# Clock_group.net
KiCad netlist of a schematic drawn in Altium Designer
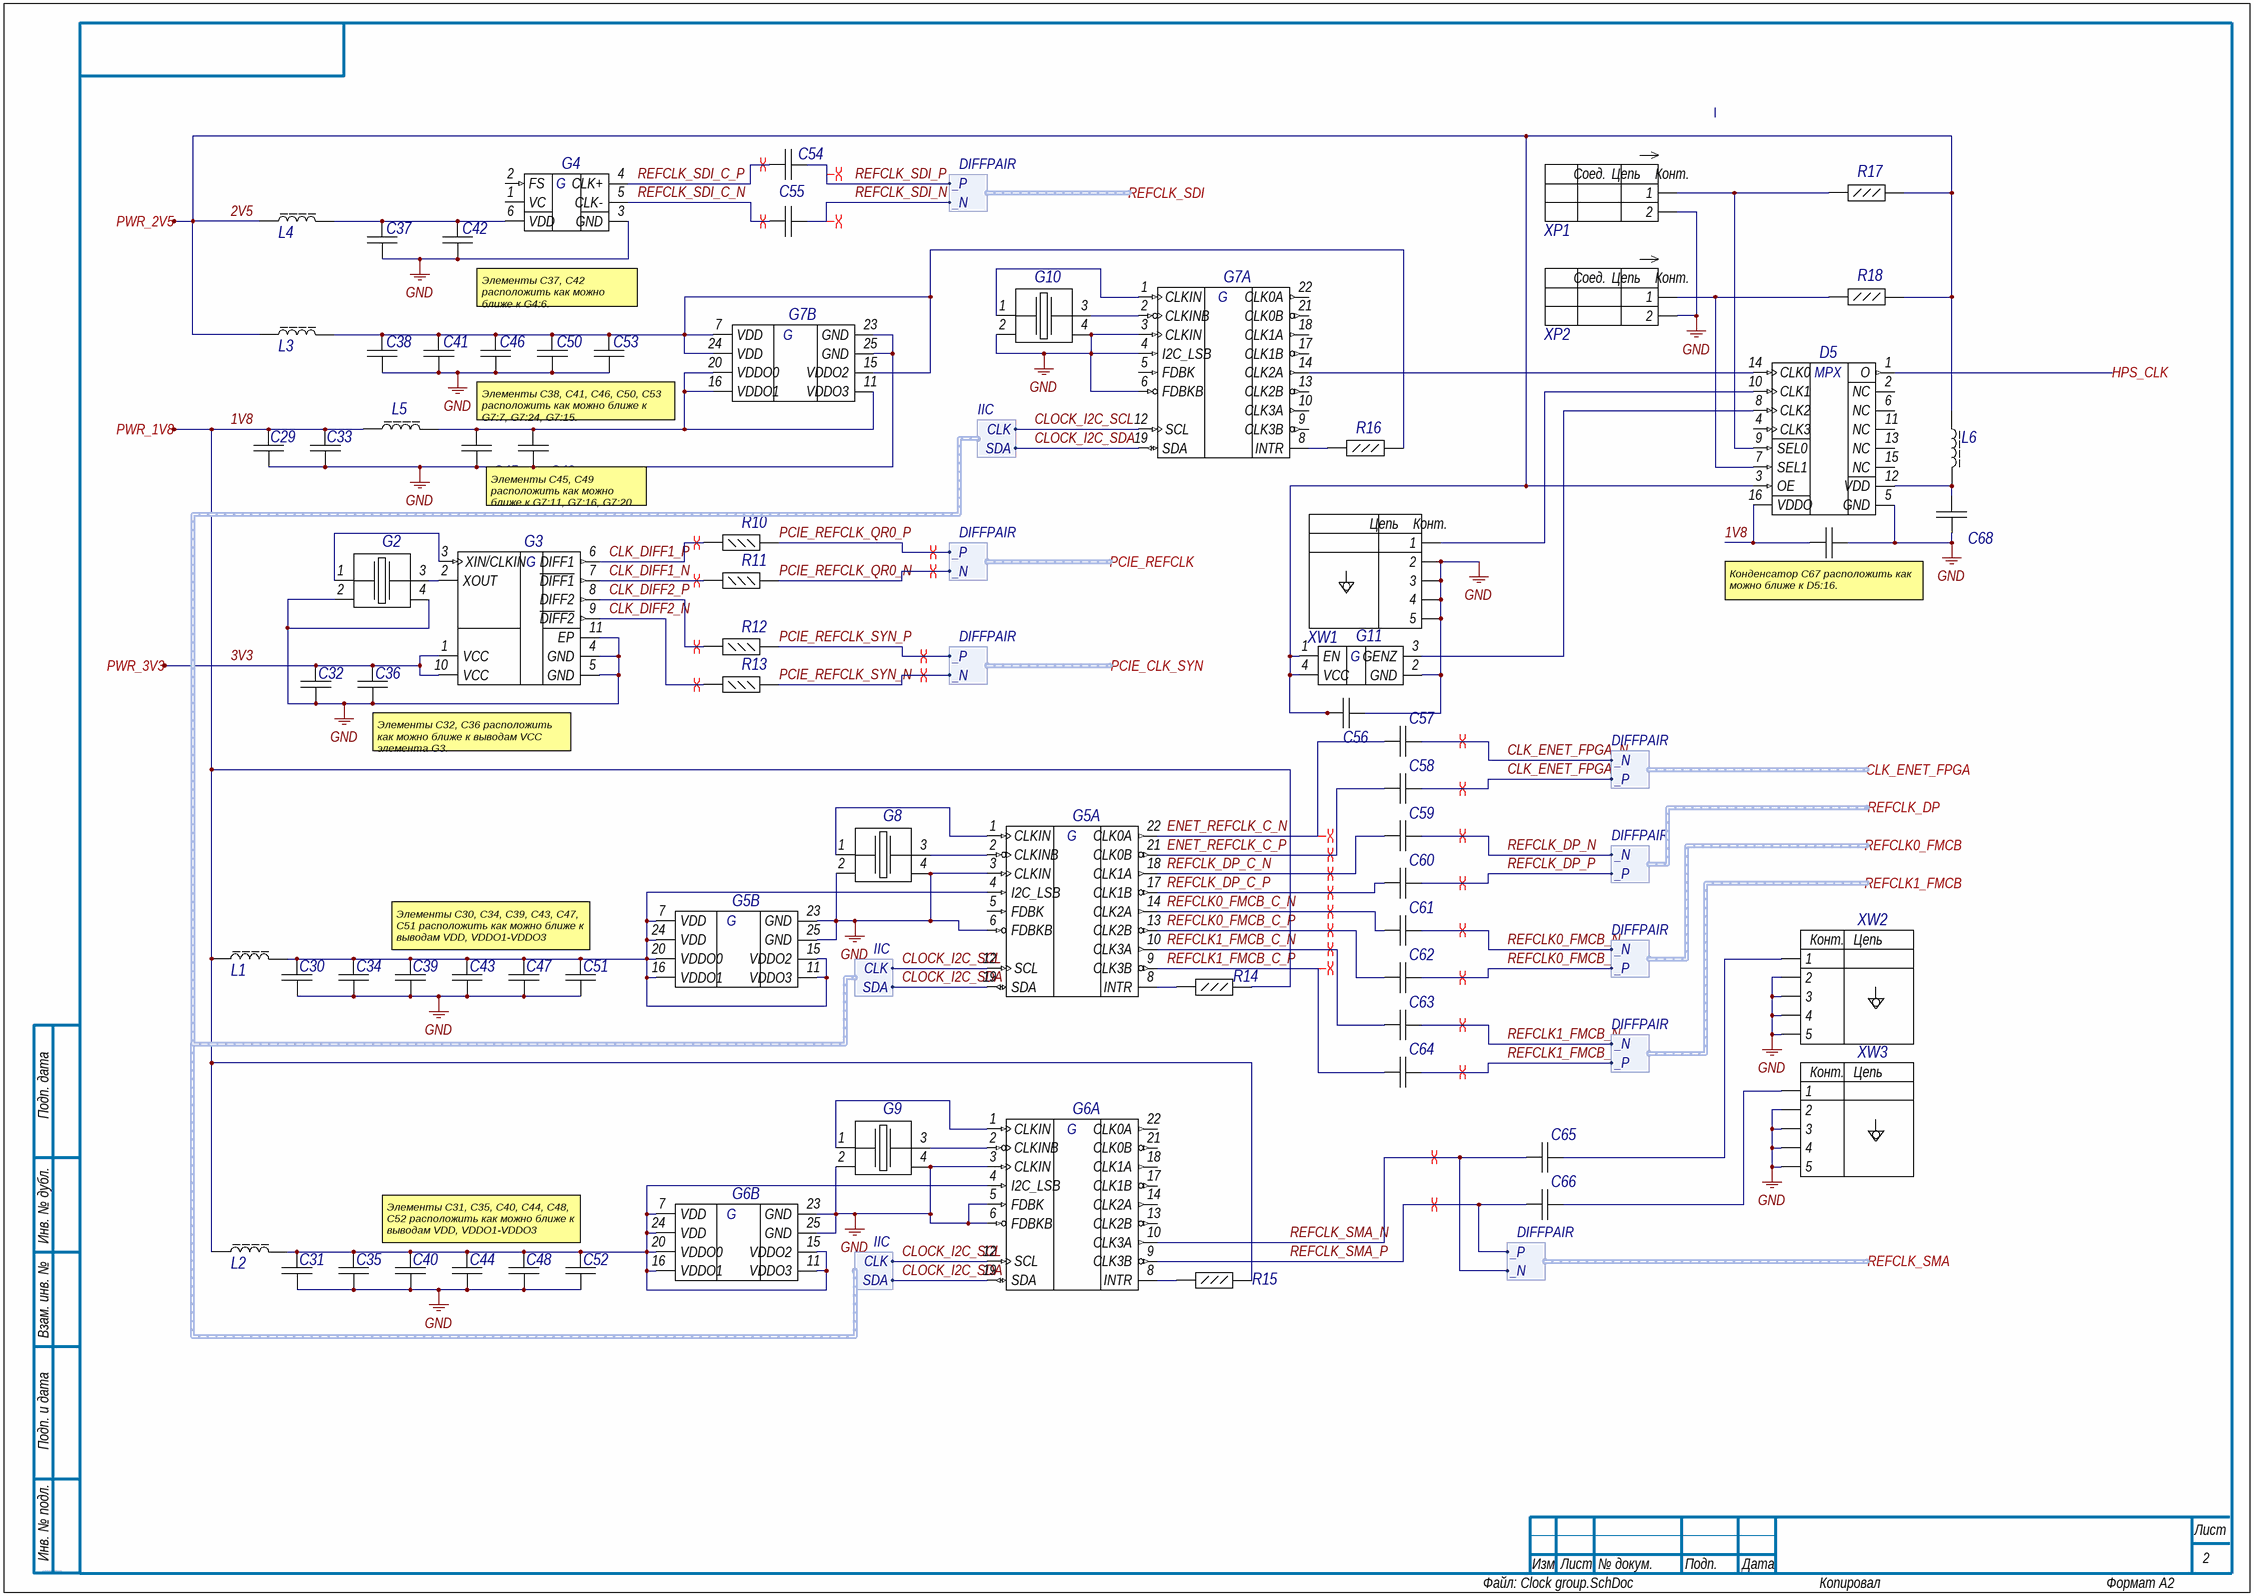
[diagram p0: Clock group.SchDoc]

(export (version "E")
  (design (tool "Eeschema 10.0.6"))
  (components
    (comp (ref "C29")
      (value "C1005X7R1E104M")
      (footprint "CAPC1005X55X10LL05")
      (description "Chip Capacitor, 0.1 uF, +/- 20%, 25 V, -55 to 125 degC, 0402 (1005 Metric), RoHS, Tape and Reel")
      (fields (field (name "TOLERANCE") "20%"))
      (libsource (lib "MiniPC DB") (part "CAP_NP"))
    )
    (comp (ref "C30")
      (value "C1005X7R1E104M")
      (footprint "CAPC1005X55X10LL05")
      (description "Chip Capacitor, 0.1 uF, +/- 20%, 25 V, -55 to 125 degC, 0402 (1005 Metric), RoHS, Tape and Reel")
      (fields (field (name "TOLERANCE") "20%"))
      (libsource (lib "MiniPC DB") (part "CAP_NP"))
    )
    (comp (ref "C31")
      (value "C1005X7R1E104M")
      (footprint "CAPC1005X55X10LL05")
      (description "Chip Capacitor, 0.1 uF, +/- 20%, 25 V, -55 to 125 degC, 0402 (1005 Metric), RoHS, Tape and Reel")
      (fields (field (name "TOLERANCE") "20%"))
      (libsource (lib "MiniPC DB") (part "CAP_NP"))
    )
    (comp (ref "C32")
      (value "C1005X7R1E104M")
      (footprint "CAPC1005X55X10LL05")
      (description "Chip Capacitor, 0.1 uF, +/- 20%, 25 V, -55 to 125 degC, 0402 (1005 Metric), RoHS, Tape and Reel")
      (fields (field (name "TOLERANCE") "20%"))
      (libsource (lib "MiniPC DB") (part "CAP_NP"))
    )
    (comp (ref "C33")
      (value "C1005X7R1E104M")
      (footprint "CAPC1005X55X10LL05")
      (description "Chip Capacitor, 0.1 uF, +/- 20%, 25 V, -55 to 125 degC, 0402 (1005 Metric), RoHS, Tape and Reel")
      (fields (field (name "TOLERANCE") "20%"))
      (libsource (lib "MiniPC DB") (part "CAP_NP"))
    )
    (comp (ref "C34")
      (value "C1005X7R1E104M")
      (footprint "CAPC1005X55X10LL05")
      (description "Chip Capacitor, 0.1 uF, +/- 20%, 25 V, -55 to 125 degC, 0402 (1005 Metric), RoHS, Tape and Reel")
      (fields (field (name "TOLERANCE") "20%"))
      (libsource (lib "MiniPC DB") (part "CAP_NP"))
    )
    (comp (ref "C35")
      (value "C1005X7R1E104M")
      (footprint "CAPC1005X55X10LL05")
      (description "Chip Capacitor, 0.1 uF, +/- 20%, 25 V, -55 to 125 degC, 0402 (1005 Metric), RoHS, Tape and Reel")
      (fields (field (name "TOLERANCE") "20%"))
      (libsource (lib "MiniPC DB") (part "CAP_NP"))
    )
    (comp (ref "C36")
      (value "GRM188R61A225KE34x")
      (footprint "CAPC1608X90X35ML10T15")
      (description "Chip Capacitor, 2.2 uF, +/- 10%, 10 V, -55 to 85 degC, 0603 (1608 Metric), RoHS, Tape and Reel")
      (fields (field (name "TOLERANCE") "10%"))
      (libsource (lib "MiniPC DB") (part "CAP_NP"))
    )
    (comp (ref "C37")
      (value "C2012X5R1C106K085AC")
      (footprint "CAPC2013X100X20NL20")
      (description "Chip Capacitor, 10 uF, +/- 10%, 16 V, -55 to 85 degC, 0805 (2012 Metric), RoHS, Tape and Reel")
      (fields (field (name "TOLERANCE") "10%"))
      (libsource (lib "MiniPC DB") (part "CAP_NP"))
    )
    (comp (ref "C38")
      (value "C1005X7R1E104M")
      (footprint "CAPC1005X55X10LL05")
      (description "Chip Capacitor, 0.1 uF, +/- 20%, 25 V, -55 to 125 degC, 0402 (1005 Metric), RoHS, Tape and Reel")
      (fields (field (name "TOLERANCE") "20%"))
      (libsource (lib "MiniPC DB") (part "CAP_NP"))
    )
    (comp (ref "C39")
      (value "C1005X7R1E104M")
      (footprint "CAPC1005X55X10LL05")
      (description "Chip Capacitor, 0.1 uF, +/- 20%, 25 V, -55 to 125 degC, 0402 (1005 Metric), RoHS, Tape and Reel")
      (fields (field (name "TOLERANCE") "20%"))
      (libsource (lib "MiniPC DB") (part "CAP_NP"))
    )
    (comp (ref "C40")
      (value "C1005X7R1E104M")
      (footprint "CAPC1005X55X10LL05")
      (description "Chip Capacitor, 0.1 uF, +/- 20%, 25 V, -55 to 125 degC, 0402 (1005 Metric), RoHS, Tape and Reel")
      (fields (field (name "TOLERANCE") "20%"))
      (libsource (lib "MiniPC DB") (part "CAP_NP"))
    )
    (comp (ref "C41")
      (value "C1005X7R1E104M")
      (footprint "CAPC1005X55X10LL05")
      (description "Chip Capacitor, 0.1 uF, +/- 20%, 25 V, -55 to 125 degC, 0402 (1005 Metric), RoHS, Tape and Reel")
      (fields (field (name "TOLERANCE") "20%"))
      (libsource (lib "MiniPC DB") (part "CAP_NP"))
    )
    (comp (ref "C42")
      (value "C1005X7R1E104M")
      (footprint "CAPC1005X55X10LL05")
      (description "Chip Capacitor, 0.1 uF, +/- 20%, 25 V, -55 to 125 degC, 0402 (1005 Metric), RoHS, Tape and Reel")
      (fields (field (name "TOLERANCE") "20%"))
      (libsource (lib "MiniPC DB") (part "CAP_NP"))
    )
    (comp (ref "C43")
      (value "C1005X7R1E104M")
      (footprint "CAPC1005X55X10LL05")
      (description "Chip Capacitor, 0.1 uF, +/- 20%, 25 V, -55 to 125 degC, 0402 (1005 Metric), RoHS, Tape and Reel")
      (fields (field (name "TOLERANCE") "20%"))
      (libsource (lib "MiniPC DB") (part "CAP_NP"))
    )
    (comp (ref "C44")
      (value "C1005X7R1E104M")
      (footprint "CAPC1005X55X10LL05")
      (description "Chip Capacitor, 0.1 uF, +/- 20%, 25 V, -55 to 125 degC, 0402 (1005 Metric), RoHS, Tape and Reel")
      (fields (field (name "TOLERANCE") "20%"))
      (libsource (lib "MiniPC DB") (part "CAP_NP"))
    )
    (comp (ref "C45")
      (value "C1005X7R1E104M")
      (footprint "CAPC1005X55X10LL05")
      (description "Chip Capacitor, 0.1 uF, +/- 20%, 25 V, -55 to 125 degC, 0402 (1005 Metric), RoHS, Tape and Reel")
      (fields (field (name "TOLERANCE") "20%"))
      (libsource (lib "MiniPC DB") (part "CAP_NP"))
    )
    (comp (ref "C46")
      (value "C1005X7R1E104M")
      (footprint "CAPC1005X55X10LL05")
      (description "Chip Capacitor, 0.1 uF, +/- 20%, 25 V, -55 to 125 degC, 0402 (1005 Metric), RoHS, Tape and Reel")
      (fields (field (name "TOLERANCE") "20%"))
      (libsource (lib "MiniPC DB") (part "CAP_NP"))
    )
    (comp (ref "C47")
      (value "C1005X7R1E104M")
      (footprint "CAPC1005X55X10LL05")
      (description "Chip Capacitor, 0.1 uF, +/- 20%, 25 V, -55 to 125 degC, 0402 (1005 Metric), RoHS, Tape and Reel")
      (fields (field (name "TOLERANCE") "20%"))
      (libsource (lib "MiniPC DB") (part "CAP_NP"))
    )
    (comp (ref "C48")
      (value "C1005X7R1E104M")
      (footprint "CAPC1005X55X10LL05")
      (description "Chip Capacitor, 0.1 uF, +/- 20%, 25 V, -55 to 125 degC, 0402 (1005 Metric), RoHS, Tape and Reel")
      (fields (field (name "TOLERANCE") "20%"))
      (libsource (lib "MiniPC DB") (part "CAP_NP"))
    )
    (comp (ref "C49")
      (value "C1005X7R1E104M")
      (footprint "CAPC1005X55X10LL05")
      (description "Chip Capacitor, 0.1 uF, +/- 20%, 25 V, -55 to 125 degC, 0402 (1005 Metric), RoHS, Tape and Reel")
      (fields (field (name "TOLERANCE") "20%"))
      (libsource (lib "MiniPC DB") (part "CAP_NP"))
    )
    (comp (ref "C50")
      (value "C1005X7R1E104M")
      (footprint "CAPC1005X55X10LL05")
      (description "Chip Capacitor, 0.1 uF, +/- 20%, 25 V, -55 to 125 degC, 0402 (1005 Metric), RoHS, Tape and Reel")
      (fields (field (name "TOLERANCE") "20%"))
      (libsource (lib "MiniPC DB") (part "CAP_NP"))
    )
    (comp (ref "C51")
      (value "C1005X7R1E104M")
      (footprint "CAPC1005X55X10LL05")
      (description "Chip Capacitor, 0.1 uF, +/- 20%, 25 V, -55 to 125 degC, 0402 (1005 Metric), RoHS, Tape and Reel")
      (fields (field (name "TOLERANCE") "20%"))
      (libsource (lib "MiniPC DB") (part "CAP_NP"))
    )
    (comp (ref "C52")
      (value "C1005X7R1E104M")
      (footprint "CAPC1005X55X10LL05")
      (description "Chip Capacitor, 0.1 uF, +/- 20%, 25 V, -55 to 125 degC, 0402 (1005 Metric), RoHS, Tape and Reel")
      (fields (field (name "TOLERANCE") "20%"))
      (libsource (lib "MiniPC DB") (part "CAP_NP"))
    )
    (comp (ref "C53")
      (value "C1005X7R1E104M")
      (footprint "CAPC1005X55X10LL05")
      (description "Chip Capacitor, 0.1 uF, +/- 20%, 25 V, -55 to 125 degC, 0402 (1005 Metric), RoHS, Tape and Reel")
      (fields (field (name "TOLERANCE") "20%"))
      (libsource (lib "MiniPC DB") (part "CAP_NP"))
    )
    (comp (ref "C54")
      (value "C1005X7R1E104M")
      (footprint "CAPC1005X55X10LL05")
      (description "Chip Capacitor, 0.1 uF, +/- 20%, 25 V, -55 to 125 degC, 0402 (1005 Metric), RoHS, Tape and Reel")
      (fields (field (name "TOLERANCE") "20%"))
      (libsource (lib "MiniPC DB") (part "CAP_NP"))
    )
    (comp (ref "C55")
      (value "C1005X7R1E104M")
      (footprint "CAPC1005X55X10LL05")
      (description "Chip Capacitor, 0.1 uF, +/- 20%, 25 V, -55 to 125 degC, 0402 (1005 Metric), RoHS, Tape and Reel")
      (fields (field (name "TOLERANCE") "20%"))
      (libsource (lib "MiniPC DB") (part "CAP_NP"))
    )
    (comp (ref "C56")
      (value "GRM155R71H103KA88D")
      (footprint "CAPC1005X55X25ML05T10")
      (description "Chip Capacitor, 10 nF, +/- 10%, 50 V, -55 to 125 degC, 0402 (1005 Metric), RoHS, Tape and Reel")
      (fields (field (name "TOLERANCE") "10%") (field (name "MANUFACTURER") "Basic Passives"))
      (libsource (lib "MiniPC DB") (part "CAP_NP"))
    )
    (comp (ref "C57")
      (value "C1005X7R1E104M")
      (footprint "CAPC1005X55X10LL05")
      (description "Chip Capacitor, 0.1 uF, +/- 20%, 25 V, -55 to 125 degC, 0402 (1005 Metric), RoHS, Tape and Reel")
      (fields (field (name "TOLERANCE") "20%"))
      (libsource (lib "MiniPC DB") (part "CAP_NP"))
    )
    (comp (ref "C58")
      (value "C1005X7R1E104M")
      (footprint "CAPC1005X55X10LL05")
      (description "Chip Capacitor, 0.1 uF, +/- 20%, 25 V, -55 to 125 degC, 0402 (1005 Metric), RoHS, Tape and Reel")
      (fields (field (name "TOLERANCE") "20%"))
      (libsource (lib "MiniPC DB") (part "CAP_NP"))
    )
    (comp (ref "C59")
      (value "C1005X7R1E104M")
      (footprint "CAPC1005X55X10LL05")
      (description "Chip Capacitor, 0.1 uF, +/- 20%, 25 V, -55 to 125 degC, 0402 (1005 Metric), RoHS, Tape and Reel")
      (fields (field (name "TOLERANCE") "20%"))
      (libsource (lib "MiniPC DB") (part "CAP_NP"))
    )
    (comp (ref "C60")
      (value "C1005X7R1E104M")
      (footprint "CAPC1005X55X10LL05")
      (description "Chip Capacitor, 0.1 uF, +/- 20%, 25 V, -55 to 125 degC, 0402 (1005 Metric), RoHS, Tape and Reel")
      (fields (field (name "TOLERANCE") "20%"))
      (libsource (lib "MiniPC DB") (part "CAP_NP"))
    )
    (comp (ref "C61")
      (value "C1005X7R1E104M")
      (footprint "CAPC1005X55X10LL05")
      (description "Chip Capacitor, 0.1 uF, +/- 20%, 25 V, -55 to 125 degC, 0402 (1005 Metric), RoHS, Tape and Reel")
      (fields (field (name "TOLERANCE") "20%"))
      (libsource (lib "MiniPC DB") (part "CAP_NP"))
    )
    (comp (ref "C62")
      (value "C1005X7R1E104M")
      (footprint "CAPC1005X55X10LL05")
      (description "Chip Capacitor, 0.1 uF, +/- 20%, 25 V, -55 to 125 degC, 0402 (1005 Metric), RoHS, Tape and Reel")
      (fields (field (name "TOLERANCE") "20%"))
      (libsource (lib "MiniPC DB") (part "CAP_NP"))
    )
    (comp (ref "C63")
      (value "C1005X7R1E104M")
      (footprint "CAPC1005X55X10LL05")
      (description "Chip Capacitor, 0.1 uF, +/- 20%, 25 V, -55 to 125 degC, 0402 (1005 Metric), RoHS, Tape and Reel")
      (fields (field (name "TOLERANCE") "20%"))
      (libsource (lib "MiniPC DB") (part "CAP_NP"))
    )
    (comp (ref "C64")
      (value "C1005X7R1E104M")
      (footprint "CAPC1005X55X10LL05")
      (description "Chip Capacitor, 0.1 uF, +/- 20%, 25 V, -55 to 125 degC, 0402 (1005 Metric), RoHS, Tape and Reel")
      (fields (field (name "TOLERANCE") "20%"))
      (libsource (lib "MiniPC DB") (part "CAP_NP"))
    )
    (comp (ref "C65")
      (value "C1005X7R1E104M")
      (footprint "CAPC1005X55X10LL05")
      (description "Chip Capacitor, 0.1 uF, +/- 20%, 25 V, -55 to 125 degC, 0402 (1005 Metric), RoHS, Tape and Reel")
      (fields (field (name "TOLERANCE") "20%"))
      (libsource (lib "MiniPC DB") (part "CAP_NP"))
    )
    (comp (ref "C66")
      (value "C1005X7R1E104M")
      (footprint "CAPC1005X55X10LL05")
      (description "Chip Capacitor, 0.1 uF, +/- 20%, 25 V, -55 to 125 degC, 0402 (1005 Metric), RoHS, Tape and Reel")
      (fields (field (name "TOLERANCE") "20%"))
      (libsource (lib "MiniPC DB") (part "CAP_NP"))
    )
    (comp (ref "C67")
      (value "C1005X7R1E104M")
      (footprint "CAPC1005X55X10LL05")
      (description "Chip Capacitor, 0.1 uF, +/- 20%, 25 V, -55 to 125 degC, 0402 (1005 Metric), RoHS, Tape and Reel")
      (fields (field (name "TOLERANCE") "20%"))
      (libsource (lib "MiniPC DB") (part "CAP_NP"))
    )
    (comp (ref "C68")
      (value "C1005X7R1E104M")
      (footprint "CAPC1005X55X10LL05")
      (description "Chip Capacitor, 0.1 uF, +/- 20%, 25 V, -55 to 125 degC, 0402 (1005 Metric), RoHS, Tape and Reel")
      (fields (field (name "TOLERANCE") "20%"))
      (libsource (lib "MiniPC DB") (part "CAP_NP"))
    )
    (comp (ref "D5")
      (value "ICS83054AGILF")
      (footprint "IDT-TSSOP-16_M")
      (description "Single-Ended Multiplexer, 2.375 to 3.465 V, -40 to 85 degC, 16-Pin TSSOP, RoHS, Tube")
      (fields (field (name "MANUFACTURER") "IDT"))
      (libsource (lib "MiniPC DB") (part "ICS83054I"))
    )
    (comp (ref "G2")
      (value "FA-128 25.0000MB-C")
      (footprint "EPSON-FA-128_V")
      (description "Range Crystal Unit, 25 MHz, -40 to 85 degC, 4-Pin SMD, RoHS, Tape and Reel")
      (libsource (lib "MiniPC DB") (part "OSC_4K"))
    )
    (comp (ref "G3")
      (value "Si52112-A1-GM2")
      (footprint "SLAB-TDFN-10_L")
      (fields (field (name "MANUFACTURER") "Silicon Labs"))
      (libsource (lib "MiniPC DB") (part "Si52112"))
    )
    (comp (ref "G4")
      (value "516FHA000132AAG")
      (footprint "SLAB-DFN-6-5000X7000DE_A_V")
      (fields (field (name "MANUFACTURER") "Silicon Labs"))
      (libsource (lib "MiniPC DB") (part "516FHA"))
    )
    (comp (ref "G5")
      (value "Si5338B-B03799-GM")
      (footprint "SLAB-QFN-24-2550x2550TP_V")
      (fields (field (name "MANUFACTURER") "Silicon Labs"))
      (libsource (lib "MiniPC DB") (part "Si5338"))
    )
    (comp (ref "G6")
      (value "Si5338B-B03799-GM")
      (footprint "SLAB-QFN-24-2550x2550TP_V")
      (fields (field (name "MANUFACTURER") "Silicon Labs"))
      (libsource (lib "MiniPC DB") (part "Si5338"))
    )
    (comp (ref "G7")
      (value "Si5338C-B03798-GM")
      (footprint "SLAB-QFN-24-2550x2550TP_V")
      (fields (field (name "MANUFACTURER") "Silicon Labs"))
      (libsource (lib "MiniPC DB") (part "Si5338"))
    )
    (comp (ref "G8")
      (value "FA-128 25.0000MB-C")
      (footprint "EPSON-FA-128_V")
      (description "Range Crystal Unit, 25 MHz, -40 to 85 degC, 4-Pin SMD, RoHS, Tape and Reel")
      (libsource (lib "MiniPC DB") (part "OSC_4K"))
    )
    (comp (ref "G9")
      (value "FA-128 25.0000MB-C")
      (footprint "EPSON-FA-128_V")
      (description "Range Crystal Unit, 25 MHz, -40 to 85 degC, 4-Pin SMD, RoHS, Tape and Reel")
      (libsource (lib "MiniPC DB") (part "OSC_4K"))
    )
    (comp (ref "G10")
      (value "FA-128 25.0000MB-C")
      (footprint "EPSON-FA-128_V")
      (description "Range Crystal Unit, 25 MHz, -40 to 85 degC, 4-Pin SMD, RoHS, Tape and Reel")
      (libsource (lib "MiniPC DB") (part "OSC_4K"))
    )
    (comp (ref "G11")
      (value "ASE2-33.000MHZ-ET")
      (footprint "ABRA-ASE2_V")
      (fields (field (name "MANUFACTURER") "Abracon"))
      (libsource (lib "MiniPC DB") (part "ASE2"))
    )
    (comp (ref "L1")
      (value "BLM15AG221SN1J")
      (footprint "MURA-BLM15-CHIP-2_V")
      (fields (field (name "MANUFACTURER") "Murata"))
      (libsource (lib "MiniPC DB") (part "Choke"))
    )
    (comp (ref "L2")
      (value "BLM15AG221SN1x")
      (footprint "MURA-BLM15AG221SN1x_V")
      (description "Chip Bead, 220 Ohm, +/- 25 %, 100 MHz, 300 mA, -55 to 125 degC, 0402 (1005 Metric), RoHS")
      (fields (field (name "TOLERANCE") "25%"))
      (libsource (lib "MiniPC DB") (part "Choke"))
    )
    (comp (ref "L3")
      (value "742792780")
      (footprint "SMD-0402")
      (description "SMD EMI Suppression Ferrite Bead WE-CBF, Z = 220 Ohm")
      (libsource (lib "") (part "Choke_1"))
    )
    (comp (ref "L4")
      (value "BLM15AG221SN1x")
      (footprint "MURA-BLM15AG221SN1x_V")
      (description "Chip Bead, 220 Ohm, +/- 25 %, 100 MHz, 300 mA, -55 to 125 degC, 0402 (1005 Metric), RoHS")
      (fields (field (name "TOLERANCE") "25%"))
      (libsource (lib "") (part "Choke_1"))
    )
    (comp (ref "L5")
      (value "742792780")
      (footprint "SMD-0402")
      (description "SMD EMI Suppression Ferrite Bead WE-CBF, Z = 220 Ohm")
      (libsource (lib "MiniPC DB") (part "Choke"))
    )
    (comp (ref "L6")
      (value "742792780")
      (footprint "SMD-0402")
      (description "SMD EMI Suppression Ferrite Bead WE-CBF, Z = 220 Ohm")
      (libsource (lib "") (part "Choke_2"))
    )
    (comp (ref "R10")
      (value "ERJ-2GE0R00X")
      (footprint "RESC1005X40X25LL05T05")
      (description "Chip Resistor, 0 mOhm, +/- 5%, 100 mW, -55 to 155 degC, 0402 (1005 Metric), RoHS, Tape and Reel")
      (fields (field (name "TOLERANCE") "5%") (field (name "MANUFACTURER") "Basic Passives"))
      (libsource (lib "MiniPC DB") (part "RES-0.05"))
    )
    (comp (ref "R11")
      (value "ERJ-2GE0R00X")
      (footprint "RESC1005X40X25LL05T05")
      (description "Chip Resistor, 0 mOhm, +/- 5%, 100 mW, -55 to 155 degC, 0402 (1005 Metric), RoHS, Tape and Reel")
      (fields (field (name "TOLERANCE") "5%") (field (name "MANUFACTURER") "Basic Passives"))
      (libsource (lib "MiniPC DB") (part "RES-0.05"))
    )
    (comp (ref "R12")
      (value "ERJ-2GE0R00X")
      (footprint "RESC1005X40X25LL05T05")
      (description "Chip Resistor, 0 mOhm, +/- 5%, 100 mW, -55 to 155 degC, 0402 (1005 Metric), RoHS, Tape and Reel")
      (fields (field (name "TOLERANCE") "5%") (field (name "MANUFACTURER") "Basic Passives"))
      (libsource (lib "MiniPC DB") (part "RES-0.05"))
    )
    (comp (ref "R13")
      (value "ERJ-2GE0R00X")
      (footprint "RESC1005X40X25LL05T05")
      (description "Chip Resistor, 0 mOhm, +/- 5%, 100 mW, -55 to 155 degC, 0402 (1005 Metric), RoHS, Tape and Reel")
      (fields (field (name "TOLERANCE") "5%") (field (name "MANUFACTURER") "Basic Passives"))
      (libsource (lib "MiniPC DB") (part "RES-0.05"))
    )
    (comp (ref "R14")
      (value "ERJ-2RKF4701X")
      (footprint "RESC1005X40X25LL05T05")
      (description "Chip Resistor, 4.7 KOhm, +/- 1%, 0.1 W, -55 to 155 degC, 0402 (1005 Metric), RoHS, Tape and Reel")
      (fields (field (name "TOLERANCE") "1%"))
      (libsource (lib "") (part "RES-0.05_1"))
    )
    (comp (ref "R15")
      (value "ERJ-2RKF4701X")
      (footprint "RESC1005X40X25LL05T05")
      (description "Chip Resistor, 4.7 KOhm, +/- 1%, 0.1 W, -55 to 155 degC, 0402 (1005 Metric), RoHS, Tape and Reel")
      (fields (field (name "TOLERANCE") "1%"))
      (libsource (lib "") (part "RES-0.05_1"))
    )
    (comp (ref "R16")
      (value "ERJ-2RKF1001X")
      (footprint "RESC1005X40X25LL05T05")
      (description "Chip Resistor, 1 KOhm, +/- 1%, 100 mW, -55 to 155 degC, 0402 (1005 Metric), RoHS, Tape and Reel")
      (fields (field (name "TOLERANCE") "1%") (field (name "MANUFACTURER") "Basic Passives"))
      (libsource (lib "") (part "RES-0.05_1"))
    )
    (comp (ref "R17")
      (value "ERJ-2RKF1001X")
      (footprint "RESC1005X40X25LL05T05")
      (description "Chip Resistor, 1 KOhm, +/- 1%, 100 mW, -55 to 155 degC, 0402 (1005 Metric), RoHS, Tape and Reel")
      (fields (field (name "TOLERANCE") "1%") (field (name "MANUFACTURER") "Basic Passives"))
      (libsource (lib "") (part "RES-0.05_1"))
    )
    (comp (ref "R18")
      (value "ERJ-2RKF1001X")
      (footprint "RESC1005X40X25LL05T05")
      (description "Chip Resistor, 1 KOhm, +/- 1%, 100 mW, -55 to 155 degC, 0402 (1005 Metric), RoHS, Tape and Reel")
      (fields (field (name "TOLERANCE") "1%") (field (name "MANUFACTURER") "Basic Passives"))
      (libsource (lib "") (part "RES-0.05_1"))
    )
    (comp (ref "XP1")
      (value "613 002 111 21")
      (footprint "WE-61300211121_V")
      (fields (field (name "MANUFACTURER") "Wuerth Elektronik"))
      (libsource (lib "MiniPC DB") (part "VILKA_2K"))
    )
    (comp (ref "XP2")
      (value "613 002 111 21")
      (footprint "WE-61300211121_V")
      (fields (field (name "MANUFACTURER") "Wuerth Elektronik"))
      (libsource (lib "MiniPC DB") (part "VILKA_2K"))
    )
    (comp (ref "XW1")
      (value "LTI-SASF54GT")
      (footprint "LHT-LTI-SASF54GT_V")
      (description "SMA Connector, Pitch 2.54 mm, 1 Position, Height 9.5 mm, Tail Length 4 mm, RoHS")
      (fields (field (name "MANUFACTURER") "Lighthorse Technologies Inc."))
      (libsource (lib "") (part "ROZETKA_SMA5_PCB_1"))
    )
    (comp (ref "XW2")
      (value "LTI-SASF54GT")
      (footprint "LHT-LTI-SASF54GT_V")
      (description "SMA Connector, Pitch 2.54 mm, 1 Position, Height 9.5 mm, Tail Length 4 mm, RoHS")
      (fields (field (name "MANUFACTURER") "Lighthorse Technologies Inc."))
      (libsource (lib "MiniPC DB") (part "ROZETKA_SMA5_PCB"))
    )
    (comp (ref "XW3")
      (value "LTI-SASF54GT")
      (footprint "LHT-LTI-SASF54GT_V")
      (description "SMA Connector, Pitch 2.54 mm, 1 Position, Height 9.5 mm, Tail Length 4 mm, RoHS")
      (fields (field (name "MANUFACTURER") "Lighthorse Technologies Inc."))
      (libsource (lib "MiniPC DB") (part "ROZETKA_SMA5_PCB"))
    )
  )
  (nets
    (net (code "3") (name "/1V8") (class "Default")
      (node (ref "C29") (pin "2") (pinfunction "2_2") (pintype "passive"))
      (node (ref "C33") (pin "2") (pinfunction "2_2") (pintype "passive"))
      (node (ref "C67") (pin "2") (pinfunction "2_2") (pintype "passive"))
      (node (ref "D5") (pin "16") (pinfunction "VDDO_16") (pintype "power_in"))
      (node (ref "L1") (pin "2") (pinfunction "2_2") (pintype "passive"))
      (node (ref "L2") (pin "2") (pinfunction "2_2") (pintype "passive"))
      (node (ref "L5") (pin "2") (pinfunction "2_2") (pintype "passive"))
      (node (ref "R14") (pin "1") (pinfunction "1_1") (pintype "passive"))
      (node (ref "R15") (pin "1") (pinfunction "1_1") (pintype "passive"))
    )
    (net (code "4") (name "/2V5") (class "Default")
      (node (ref "C56") (pin "2") (pinfunction "2_2") (pintype "passive"))
      (node (ref "D5") (pin "3") (pinfunction "OE_3") (pintype "input"))
      (node (ref "G11") (pin "1") (pinfunction "EN_1") (pintype "passive"))
      (node (ref "G11") (pin "4") (pinfunction "VCC_4") (pintype "passive"))
      (node (ref "L3") (pin "2") (pinfunction "2_2") (pintype "passive"))
      (node (ref "L4") (pin "2") (pinfunction "2_2") (pintype "passive"))
      (node (ref "L6") (pin "2") (pinfunction "2_2") (pintype "passive"))
      (node (ref "R17") (pin "1") (pinfunction "1_1") (pintype "passive"))
      (node (ref "R18") (pin "1") (pinfunction "1_1") (pintype "passive"))
    )
    (net (code "5") (name "/3V3") (class "Default")
      (node (ref "C32") (pin "2") (pinfunction "2_2") (pintype "passive"))
      (node (ref "C36") (pin "2") (pinfunction "2_2") (pintype "passive"))
      (node (ref "G3") (pin "1") (pinfunction "VCC_1") (pintype "passive"))
      (node (ref "G3") (pin "10") (pinfunction "VCC_10") (pintype "passive"))
    )
    (net (code "6") (name "/CLK_DIFF1_N") (class "Default")
      (node (ref "G3") (pin "7") (pinfunction "~{DIFF1}_7") (pintype "output"))
      (node (ref "R11") (pin "1") (pinfunction "1_1") (pintype "passive"))
    )
    (net (code "7") (name "/CLK_DIFF1_P") (class "Default")
      (node (ref "G3") (pin "6") (pinfunction "DIFF1_6") (pintype "output"))
      (node (ref "R10") (pin "1") (pinfunction "1_1") (pintype "passive"))
    )
    (net (code "8") (name "/CLK_DIFF2_N") (class "Default")
      (node (ref "G3") (pin "9") (pinfunction "~{DIFF2}_9") (pintype "output"))
      (node (ref "R13") (pin "1") (pinfunction "1_1") (pintype "passive"))
    )
    (net (code "9") (name "/CLK_DIFF2_P") (class "Default")
      (node (ref "G3") (pin "8") (pinfunction "DIFF2_8") (pintype "output"))
      (node (ref "R12") (pin "1") (pinfunction "1_1") (pintype "passive"))
    )
    (net (code "10") (name "/CLK_ENET_FPGA_N") (class "Default")
      (node (ref "C57") (pin "2") (pinfunction "2_2") (pintype "passive"))
    )
    (net (code "11") (name "/CLK_ENET_FPGA_P") (class "Default")
      (node (ref "C58") (pin "2") (pinfunction "2_2") (pintype "passive"))
    )
    (net (code "12") (name "/CLOCK_I2C_SCL") (class "Default")
      (node (ref "G5") (pin "12") (pinfunction "SCL_12") (pintype "input"))
      (node (ref "G6") (pin "12") (pinfunction "SCL_12") (pintype "input"))
      (node (ref "G7") (pin "12") (pinfunction "SCL_12") (pintype "input"))
    )
    (net (code "13") (name "/CLOCK_I2C_SDA") (class "Default")
      (node (ref "G5") (pin "19") (pinfunction "SDA_19") (pintype "bidirectional"))
      (node (ref "G6") (pin "19") (pinfunction "SDA_19") (pintype "bidirectional"))
      (node (ref "G7") (pin "19") (pinfunction "SDA_19") (pintype "bidirectional"))
    )
    (net (code "14") (name "/ENET_REFCLK_C_N") (class "Default")
      (node (ref "C57") (pin "1") (pinfunction "1_1") (pintype "passive"))
      (node (ref "G5") (pin "22") (pinfunction "CLK0A_22") (pintype "output"))
    )
    (net (code "15") (name "/ENET_REFCLK_C_P") (class "Default")
      (node (ref "C58") (pin "1") (pinfunction "1_1") (pintype "passive"))
      (node (ref "G5") (pin "21") (pinfunction "CLK0B_21") (pintype "output"))
    )
    (net (code "16") (name "/HPS_CLK") (class "Default")
      (node (ref "D5") (pin "1") (pinfunction "O_1") (pintype "output"))
    )
    (net (code "17") (name "/PCIE_REFCLK_QR0_N") (class "Default")
      (node (ref "R11") (pin "2") (pinfunction "2_2") (pintype "passive"))
    )
    (net (code "18") (name "/PCIE_REFCLK_QR0_P") (class "Default")
      (node (ref "R10") (pin "2") (pinfunction "2_2") (pintype "passive"))
    )
    (net (code "19") (name "/PCIE_REFCLK_SYN_N") (class "Default")
      (node (ref "R13") (pin "2") (pinfunction "2_2") (pintype "passive"))
    )
    (net (code "20") (name "/PCIE_REFCLK_SYN_P") (class "Default")
      (node (ref "R12") (pin "2") (pinfunction "2_2") (pintype "passive"))
    )
    (net (code "21") (name "/REFCLK0_FMCB_C_N") (class "Default")
      (node (ref "C61") (pin "1") (pinfunction "1_1") (pintype "passive"))
      (node (ref "G5") (pin "14") (pinfunction "CLK2A_14") (pintype "output"))
    )
    (net (code "22") (name "/REFCLK0_FMCB_C_P") (class "Default")
      (node (ref "C62") (pin "1") (pinfunction "1_1") (pintype "passive"))
      (node (ref "G5") (pin "13") (pinfunction "CLK2B_13") (pintype "output"))
    )
    (net (code "23") (name "/REFCLK0_FMCB_N") (class "Default")
      (node (ref "C61") (pin "2") (pinfunction "2_2") (pintype "passive"))
    )
    (net (code "24") (name "/REFCLK0_FMCB_P") (class "Default")
      (node (ref "C62") (pin "2") (pinfunction "2_2") (pintype "passive"))
    )
    (net (code "25") (name "/REFCLK1_FMCB_C_N") (class "Default")
      (node (ref "C63") (pin "1") (pinfunction "1_1") (pintype "passive"))
      (node (ref "G5") (pin "10") (pinfunction "CLK3A_10") (pintype "output"))
    )
    (net (code "26") (name "/REFCLK1_FMCB_C_P") (class "Default")
      (node (ref "C64") (pin "1") (pinfunction "1_1") (pintype "passive"))
      (node (ref "G5") (pin "9") (pinfunction "CLK3B_9") (pintype "output"))
    )
    (net (code "27") (name "/REFCLK1_FMCB_N") (class "Default")
      (node (ref "C63") (pin "2") (pinfunction "2_2") (pintype "passive"))
    )
    (net (code "28") (name "/REFCLK1_FMCB_P") (class "Default")
      (node (ref "C64") (pin "2") (pinfunction "2_2") (pintype "passive"))
    )
    (net (code "29") (name "/REFCLK_DP_C_N") (class "Default")
      (node (ref "C59") (pin "1") (pinfunction "1_1") (pintype "passive"))
      (node (ref "G5") (pin "18") (pinfunction "CLK1A_18") (pintype "output"))
    )
    (net (code "30") (name "/REFCLK_DP_C_P") (class "Default")
      (node (ref "C60") (pin "1") (pinfunction "1_1") (pintype "passive"))
      (node (ref "G5") (pin "17") (pinfunction "CLK1B_17") (pintype "output"))
    )
    (net (code "31") (name "/REFCLK_DP_N") (class "Default")
      (node (ref "C59") (pin "2") (pinfunction "2_2") (pintype "passive"))
    )
    (net (code "32") (name "/REFCLK_DP_P") (class "Default")
      (node (ref "C60") (pin "2") (pinfunction "2_2") (pintype "passive"))
    )
    (net (code "33") (name "/REFCLK_SDI_C_N") (class "Default")
      (node (ref "C55") (pin "2") (pinfunction "2_2") (pintype "passive"))
      (node (ref "G4") (pin "5") (pinfunction "CLK-_5") (pintype "tri_state"))
    )
    (net (code "34") (name "/REFCLK_SDI_C_P") (class "Default")
      (node (ref "C54") (pin "2") (pinfunction "2_2") (pintype "passive"))
      (node (ref "G4") (pin "4") (pinfunction "CLK+_4") (pintype "tri_state"))
    )
    (net (code "35") (name "/REFCLK_SDI_N") (class "Default")
      (node (ref "C55") (pin "1") (pinfunction "1_1") (pintype "passive"))
    )
    (net (code "36") (name "/REFCLK_SDI_P") (class "Default")
      (node (ref "C54") (pin "1") (pinfunction "1_1") (pintype "passive"))
    )
    (net (code "37") (name "/REFCLK_SMA_N") (class "Default")
      (node (ref "C65") (pin "1") (pinfunction "1_1") (pintype "passive"))
      (node (ref "G6") (pin "10") (pinfunction "CLK3A_10") (pintype "output"))
    )
    (net (code "38") (name "/REFCLK_SMA_P") (class "Default")
      (node (ref "C66") (pin "1") (pinfunction "1_1") (pintype "passive"))
      (node (ref "G6") (pin "9") (pinfunction "CLK3B_9") (pintype "output"))
    )
    (net (code "41") (name "GND") (class "Default")
      (node (ref "C29") (pin "1") (pinfunction "1_1") (pintype "passive"))
      (node (ref "C30") (pin "2") (pinfunction "2_2") (pintype "passive"))
      (node (ref "C31") (pin "2") (pinfunction "2_2") (pintype "passive"))
      (node (ref "C32") (pin "1") (pinfunction "1_1") (pintype "passive"))
      (node (ref "C33") (pin "1") (pinfunction "1_1") (pintype "passive"))
      (node (ref "C34") (pin "2") (pinfunction "2_2") (pintype "passive"))
      (node (ref "C35") (pin "2") (pinfunction "2_2") (pintype "passive"))
      (node (ref "C36") (pin "1") (pinfunction "1_1") (pintype "passive"))
      (node (ref "C37") (pin "1") (pinfunction "1_1") (pintype "passive"))
      (node (ref "C38") (pin "1") (pinfunction "1_1") (pintype "passive"))
      (node (ref "C39") (pin "2") (pinfunction "2_2") (pintype "passive"))
      (node (ref "C40") (pin "2") (pinfunction "2_2") (pintype "passive"))
      (node (ref "C41") (pin "1") (pinfunction "1_1") (pintype "passive"))
      (node (ref "C42") (pin "1") (pinfunction "1_1") (pintype "passive"))
      (node (ref "C43") (pin "2") (pinfunction "2_2") (pintype "passive"))
      (node (ref "C44") (pin "2") (pinfunction "2_2") (pintype "passive"))
      (node (ref "C45") (pin "1") (pinfunction "1_1") (pintype "passive"))
      (node (ref "C46") (pin "1") (pinfunction "1_1") (pintype "passive"))
      (node (ref "C47") (pin "2") (pinfunction "2_2") (pintype "passive"))
      (node (ref "C48") (pin "2") (pinfunction "2_2") (pintype "passive"))
      (node (ref "C49") (pin "1") (pinfunction "1_1") (pintype "passive"))
      (node (ref "C50") (pin "1") (pinfunction "1_1") (pintype "passive"))
      (node (ref "C51") (pin "2") (pinfunction "2_2") (pintype "passive"))
      (node (ref "C52") (pin "2") (pinfunction "2_2") (pintype "passive"))
      (node (ref "C53") (pin "1") (pinfunction "1_1") (pintype "passive"))
      (node (ref "C56") (pin "1") (pinfunction "1_1") (pintype "passive"))
      (node (ref "C67") (pin "1") (pinfunction "1_1") (pintype "passive"))
      (node (ref "C68") (pin "1") (pinfunction "1_1") (pintype "passive"))
      (node (ref "D5") (pin "5") (pinfunction "GND_5") (pintype "passive"))
      (node (ref "G10") (pin "2") (pinfunction "GND_2") (pintype "passive"))
      (node (ref "G10") (pin "4") (pinfunction "GND_4") (pintype "passive"))
      (node (ref "G11") (pin "2") (pinfunction "GND_2") (pintype "passive"))
      (node (ref "G2") (pin "2") (pinfunction "GND_2") (pintype "passive"))
      (node (ref "G2") (pin "4") (pinfunction "GND_4") (pintype "passive"))
      (node (ref "G3") (pin "11") (pinfunction "EP_11") (pintype "passive"))
      (node (ref "G3") (pin "4") (pinfunction "GND_4") (pintype "passive"))
      (node (ref "G3") (pin "5") (pinfunction "GND_5") (pintype "passive"))
      (node (ref "G4") (pin "3") (pinfunction "GND_3") (pintype "passive"))
      (node (ref "G5") (pin "23") (pinfunction "GND_23") (pintype "passive"))
      (node (ref "G5") (pin "25") (pinfunction "GND_25") (pintype "passive"))
      (node (ref "G5") (pin "3") (pinfunction "CLKIN_3") (pintype "input"))
      (node (ref "G5") (pin "6") (pinfunction "FDBKB_6") (pintype "input"))
      (node (ref "G6") (pin "23") (pinfunction "GND_23") (pintype "passive"))
      (node (ref "G6") (pin "25") (pinfunction "GND_25") (pintype "passive"))
      (node (ref "G6") (pin "3") (pinfunction "CLKIN_3") (pintype "input"))
      (node (ref "G6") (pin "5") (pinfunction "FDBK_5") (pintype "input"))
      (node (ref "G6") (pin "6") (pinfunction "FDBKB_6") (pintype "input"))
      (node (ref "G7") (pin "23") (pinfunction "GND_23") (pintype "passive"))
      (node (ref "G7") (pin "25") (pinfunction "GND_25") (pintype "passive"))
      (node (ref "G7") (pin "3") (pinfunction "CLKIN_3") (pintype "input"))
      (node (ref "G7") (pin "4") (pinfunction "I2C_LSB_4") (pintype "input"))
      (node (ref "G7") (pin "6") (pinfunction "FDBKB_6") (pintype "input"))
      (node (ref "G8") (pin "2") (pinfunction "GND_2") (pintype "passive"))
      (node (ref "G8") (pin "4") (pinfunction "GND_4") (pintype "passive"))
      (node (ref "G9") (pin "2") (pinfunction "GND_2") (pintype "passive"))
      (node (ref "G9") (pin "4") (pinfunction "GND_4") (pintype "passive"))
      (node (ref "XP1") (pin "2") (pinfunction "2_2") (pintype "passive"))
      (node (ref "XP2") (pin "2") (pinfunction "2_2") (pintype "passive"))
      (node (ref "XW1") (pin "2") (pinfunction "2_2") (pintype "passive"))
      (node (ref "XW1") (pin "3") (pinfunction "3_3") (pintype "passive"))
      (node (ref "XW1") (pin "4") (pinfunction "4_4") (pintype "passive"))
      (node (ref "XW1") (pin "5") (pinfunction "5_5") (pintype "passive"))
      (node (ref "XW2") (pin "2") (pinfunction "2_2") (pintype "passive"))
      (node (ref "XW2") (pin "3") (pinfunction "3_3") (pintype "passive"))
      (node (ref "XW2") (pin "4") (pinfunction "4_4") (pintype "passive"))
      (node (ref "XW2") (pin "5") (pinfunction "5_5") (pintype "passive"))
      (node (ref "XW3") (pin "2") (pinfunction "2_2") (pintype "passive"))
      (node (ref "XW3") (pin "3") (pinfunction "3_3") (pintype "passive"))
      (node (ref "XW3") (pin "4") (pinfunction "4_4") (pintype "passive"))
      (node (ref "XW3") (pin "5") (pinfunction "5_5") (pintype "passive"))
    )
    (net (code "42") (name "Net-(C65-Pad2)") (class "Default")
      (node (ref "C65") (pin "2") (pinfunction "2_2") (pintype "passive"))
      (node (ref "XW2") (pin "1") (pinfunction "1_1") (pintype "passive"))
    )
    (net (code "43") (name "Net-(C66-Pad2)") (class "Default")
      (node (ref "C66") (pin "2") (pinfunction "2_2") (pintype "passive"))
      (node (ref "XW3") (pin "1") (pinfunction "1_1") (pintype "passive"))
    )
    (net (code "44") (name "Net-(D5-CLK0)") (class "Default")
      (node (ref "D5") (pin "14") (pinfunction "CLK0_14") (pintype "input"))
      (node (ref "G7") (pin "14") (pinfunction "CLK2A_14") (pintype "output"))
    )
    (net (code "45") (name "Net-(D5-CLK1)") (class "Default")
      (node (ref "D5") (pin "10") (pinfunction "CLK1_10") (pintype "input"))
      (node (ref "XW1") (pin "1") (pinfunction "1_1") (pintype "passive"))
    )
    (net (code "46") (name "Net-(D5-CLK2)") (class "Default")
      (node (ref "D5") (pin "8") (pinfunction "CLK2_8") (pintype "input"))
      (node (ref "G11") (pin "3") (pinfunction "GENZ_3") (pintype "passive"))
    )
    (net (code "47") (name "Net-(D5-SEL0)") (class "Default")
      (node (ref "D5") (pin "9") (pinfunction "SEL0_9") (pintype "input"))
      (node (ref "R17") (pin "2") (pinfunction "2_2") (pintype "passive"))
      (node (ref "XP1") (pin "1") (pinfunction "1_1") (pintype "passive"))
    )
    (net (code "48") (name "Net-(D5-SEL1)") (class "Default")
      (node (ref "D5") (pin "7") (pinfunction "SEL1_7") (pintype "input"))
      (node (ref "R18") (pin "2") (pinfunction "2_2") (pintype "passive"))
      (node (ref "XP2") (pin "1") (pinfunction "1_1") (pintype "passive"))
    )
    (net (code "49") (name "Net-(D5-VDD)") (class "Default")
      (node (ref "C68") (pin "2") (pinfunction "2_2") (pintype "passive"))
      (node (ref "D5") (pin "12") (pinfunction "VDD_12") (pintype "passive"))
      (node (ref "L6") (pin "1") (pinfunction "1_1") (pintype "passive"))
    )
    (net (code "50") (name "Net-(G2-X1)") (class "Default")
      (node (ref "G2") (pin "1") (pinfunction "X1_1") (pintype "passive"))
      (node (ref "G3") (pin "3") (pinfunction "XIN/CLKIN_3") (pintype "input"))
    )
    (net (code "51") (name "Net-(G2-X2)") (class "Default")
      (node (ref "G2") (pin "3") (pinfunction "X2_3") (pintype "passive"))
      (node (ref "G3") (pin "2") (pinfunction "XOUT_2") (pintype "passive"))
    )
    (net (code "52") (name "Net-(G4-VDD)") (class "Default")
      (node (ref "C37") (pin "2") (pinfunction "2_2") (pintype "passive"))
      (node (ref "C42") (pin "2") (pinfunction "2_2") (pintype "passive"))
      (node (ref "G4") (pin "6") (pinfunction "VDD_6") (pintype "passive"))
      (node (ref "L4") (pin "1") (pinfunction "1_1") (pintype "passive"))
    )
    (net (code "53") (name "Net-(G5A-CLKINB)") (class "Default")
      (node (ref "G5") (pin "2") (pinfunction "CLKINB_2") (pintype "input"))
      (node (ref "G8") (pin "3") (pinfunction "X2_3") (pintype "passive"))
    )
    (net (code "54") (name "Net-(G5A-I2C_LSB)") (class "Default")
      (node (ref "C30") (pin "1") (pinfunction "1_1") (pintype "passive"))
      (node (ref "C34") (pin "1") (pinfunction "1_1") (pintype "passive"))
      (node (ref "C39") (pin "1") (pinfunction "1_1") (pintype "passive"))
      (node (ref "C43") (pin "1") (pinfunction "1_1") (pintype "passive"))
      (node (ref "C47") (pin "1") (pinfunction "1_1") (pintype "passive"))
      (node (ref "C51") (pin "1") (pinfunction "1_1") (pintype "passive"))
      (node (ref "G5") (pin "11") (pinfunction "VDDO3_11") (pintype "passive"))
      (node (ref "G5") (pin "15") (pinfunction "VDDO2_15") (pintype "passive"))
      (node (ref "G5") (pin "16") (pinfunction "VDDO1_16") (pintype "passive"))
      (node (ref "G5") (pin "20") (pinfunction "VDDO0_20") (pintype "passive"))
      (node (ref "G5") (pin "24") (pinfunction "VDD_24") (pintype "passive"))
      (node (ref "G5") (pin "4") (pinfunction "I2C_LSB_4") (pintype "input"))
      (node (ref "G5") (pin "7") (pinfunction "VDD_7") (pintype "passive"))
      (node (ref "L1") (pin "1") (pinfunction "1_1") (pintype "passive"))
    )
    (net (code "55") (name "Net-(G5A-INTR)") (class "Default")
      (node (ref "G5") (pin "8") (pinfunction "INTR_8") (pintype "open_collector"))
      (node (ref "R14") (pin "2") (pinfunction "2_2") (pintype "passive"))
    )
    (net (code "56") (name "Net-(G6A-CLKINB)") (class "Default")
      (node (ref "G6") (pin "2") (pinfunction "CLKINB_2") (pintype "input"))
      (node (ref "G9") (pin "3") (pinfunction "X2_3") (pintype "passive"))
    )
    (net (code "57") (name "Net-(G6A-I2C_LSB)") (class "Default")
      (node (ref "C31") (pin "1") (pinfunction "1_1") (pintype "passive"))
      (node (ref "C35") (pin "1") (pinfunction "1_1") (pintype "passive"))
      (node (ref "C40") (pin "1") (pinfunction "1_1") (pintype "passive"))
      (node (ref "C44") (pin "1") (pinfunction "1_1") (pintype "passive"))
      (node (ref "C48") (pin "1") (pinfunction "1_1") (pintype "passive"))
      (node (ref "C52") (pin "1") (pinfunction "1_1") (pintype "passive"))
      (node (ref "G6") (pin "11") (pinfunction "VDDO3_11") (pintype "passive"))
      (node (ref "G6") (pin "15") (pinfunction "VDDO2_15") (pintype "passive"))
      (node (ref "G6") (pin "16") (pinfunction "VDDO1_16") (pintype "passive"))
      (node (ref "G6") (pin "20") (pinfunction "VDDO0_20") (pintype "passive"))
      (node (ref "G6") (pin "24") (pinfunction "VDD_24") (pintype "passive"))
      (node (ref "G6") (pin "4") (pinfunction "I2C_LSB_4") (pintype "input"))
      (node (ref "G6") (pin "7") (pinfunction "VDD_7") (pintype "passive"))
      (node (ref "L2") (pin "1") (pinfunction "1_1") (pintype "passive"))
    )
    (net (code "58") (name "Net-(G6A-INTR)") (class "Default")
      (node (ref "G6") (pin "8") (pinfunction "INTR_8") (pintype "open_collector"))
      (node (ref "R15") (pin "2") (pinfunction "2_2") (pintype "passive"))
    )
    (net (code "59") (name "Net-(G7A-INTR)") (class "Default")
      (node (ref "G7") (pin "8") (pinfunction "INTR_8") (pintype "open_collector"))
      (node (ref "R16") (pin "2") (pinfunction "2_2") (pintype "passive"))
    )
    (net (code "60") (name "Net-(G7B-VDDO0)") (class "Default")
      (node (ref "C45") (pin "2") (pinfunction "2_2") (pintype "passive"))
      (node (ref "C49") (pin "2") (pinfunction "2_2") (pintype "passive"))
      (node (ref "G7") (pin "11") (pinfunction "VDDO3_11") (pintype "passive"))
      (node (ref "G7") (pin "16") (pinfunction "VDDO1_16") (pintype "passive"))
      (node (ref "G7") (pin "20") (pinfunction "VDDO0_20") (pintype "passive"))
      (node (ref "L5") (pin "1") (pinfunction "1_1") (pintype "passive"))
    )
    (net (code "61") (name "Net-(G7B-VDDO2)") (class "Default")
      (node (ref "C38") (pin "2") (pinfunction "2_2") (pintype "passive"))
      (node (ref "C41") (pin "2") (pinfunction "2_2") (pintype "passive"))
      (node (ref "C46") (pin "2") (pinfunction "2_2") (pintype "passive"))
      (node (ref "C50") (pin "2") (pinfunction "2_2") (pintype "passive"))
      (node (ref "C53") (pin "2") (pinfunction "2_2") (pintype "passive"))
      (node (ref "G7") (pin "15") (pinfunction "VDDO2_15") (pintype "passive"))
      (node (ref "G7") (pin "24") (pinfunction "VDD_24") (pintype "passive"))
      (node (ref "G7") (pin "7") (pinfunction "VDD_7") (pintype "passive"))
      (node (ref "L3") (pin "1") (pinfunction "1_1") (pintype "passive"))
      (node (ref "R16") (pin "1") (pinfunction "1_1") (pintype "passive"))
    )
    (net (code "62") (name "Net-(G8-X1)") (class "Default")
      (node (ref "G5") (pin "1") (pinfunction "CLKIN_1") (pintype "input"))
      (node (ref "G8") (pin "1") (pinfunction "X1_1") (pintype "passive"))
    )
    (net (code "63") (name "Net-(G9-X1)") (class "Default")
      (node (ref "G6") (pin "1") (pinfunction "CLKIN_1") (pintype "input"))
      (node (ref "G9") (pin "1") (pinfunction "X1_1") (pintype "passive"))
    )
    (net (code "64") (name "Net-(G10-X1)") (class "Default")
      (node (ref "G10") (pin "1") (pinfunction "X1_1") (pintype "passive"))
      (node (ref "G7") (pin "1") (pinfunction "CLKIN_1") (pintype "input"))
    )
    (net (code "65") (name "Net-(G10-X2)") (class "Default")
      (node (ref "G10") (pin "3") (pinfunction "X2_3") (pintype "passive"))
      (node (ref "G7") (pin "2") (pinfunction "CLKINB_2") (pintype "input"))
    )
    (net (code "66") (name "unconnected-(D5-CLK3-Pad4)") (class "Default")
      (node (ref "D5") (pin "4") (pinfunction "CLK3_4") (pintype "input"))
    )
    (net (code "67") (name "unconnected-(D5-NC-Pad2)") (class "Default")
      (node (ref "D5") (pin "2") (pinfunction "NC_2") (pintype "passive"))
    )
    (net (code "68") (name "unconnected-(D5-NC-Pad6)") (class "Default")
      (node (ref "D5") (pin "6") (pinfunction "NC_6") (pintype "passive"))
    )
    (net (code "69") (name "unconnected-(D5-NC-Pad11)") (class "Default")
      (node (ref "D5") (pin "11") (pinfunction "NC_11") (pintype "passive"))
    )
    (net (code "70") (name "unconnected-(D5-NC-Pad13)") (class "Default")
      (node (ref "D5") (pin "13") (pinfunction "NC_13") (pintype "passive"))
    )
    (net (code "71") (name "unconnected-(D5-NC-Pad15)") (class "Default")
      (node (ref "D5") (pin "15") (pinfunction "NC_15") (pintype "passive"))
    )
    (net (code "72") (name "unconnected-(G4-FS-Pad2)") (class "Default")
      (node (ref "G4") (pin "2") (pinfunction "FS_2") (pintype "input"))
    )
    (net (code "73") (name "unconnected-(G4-VC-Pad1)") (class "Default")
      (node (ref "G4") (pin "1") (pinfunction "VC_1") (pintype "passive"))
    )
    (net (code "74") (name "unconnected-(G5A-FDBK-Pad5)") (class "Default")
      (node (ref "G5") (pin "5") (pinfunction "FDBK_5") (pintype "input"))
    )
    (net (code "75") (name "unconnected-(G6A-CLK0A-Pad22)") (class "Default")
      (node (ref "G6") (pin "22") (pinfunction "CLK0A_22") (pintype "output"))
    )
    (net (code "76") (name "unconnected-(G6A-CLK0B-Pad21)") (class "Default")
      (node (ref "G6") (pin "21") (pinfunction "CLK0B_21") (pintype "output"))
    )
    (net (code "77") (name "unconnected-(G6A-CLK1A-Pad18)") (class "Default")
      (node (ref "G6") (pin "18") (pinfunction "CLK1A_18") (pintype "output"))
    )
    (net (code "78") (name "unconnected-(G6A-CLK1B-Pad17)") (class "Default")
      (node (ref "G6") (pin "17") (pinfunction "CLK1B_17") (pintype "output"))
    )
    (net (code "79") (name "unconnected-(G6A-CLK2A-Pad14)") (class "Default")
      (node (ref "G6") (pin "14") (pinfunction "CLK2A_14") (pintype "output"))
    )
    (net (code "80") (name "unconnected-(G6A-CLK2B-Pad13)") (class "Default")
      (node (ref "G6") (pin "13") (pinfunction "CLK2B_13") (pintype "output"))
    )
    (net (code "81") (name "unconnected-(G7A-CLK0A-Pad22)") (class "Default")
      (node (ref "G7") (pin "22") (pinfunction "CLK0A_22") (pintype "output"))
    )
    (net (code "82") (name "unconnected-(G7A-CLK0B-Pad21)") (class "Default")
      (node (ref "G7") (pin "21") (pinfunction "CLK0B_21") (pintype "output"))
    )
    (net (code "83") (name "unconnected-(G7A-CLK1A-Pad18)") (class "Default")
      (node (ref "G7") (pin "18") (pinfunction "CLK1A_18") (pintype "output"))
    )
    (net (code "84") (name "unconnected-(G7A-CLK1B-Pad17)") (class "Default")
      (node (ref "G7") (pin "17") (pinfunction "CLK1B_17") (pintype "output"))
    )
    (net (code "85") (name "unconnected-(G7A-CLK2B-Pad13)") (class "Default")
      (node (ref "G7") (pin "13") (pinfunction "CLK2B_13") (pintype "output"))
    )
    (net (code "86") (name "unconnected-(G7A-CLK3A-Pad10)") (class "Default")
      (node (ref "G7") (pin "10") (pinfunction "CLK3A_10") (pintype "output"))
    )
    (net (code "87") (name "unconnected-(G7A-CLK3B-Pad9)") (class "Default")
      (node (ref "G7") (pin "9") (pinfunction "CLK3B_9") (pintype "output"))
    )
    (net (code "88") (name "unconnected-(G7A-FDBK-Pad5)") (class "Default")
      (node (ref "G7") (pin "5") (pinfunction "FDBK_5") (pintype "input"))
    )
  )
)
